# Gimble_Breakout.net
KiCad netlist of a schematic drawn in EAGLE
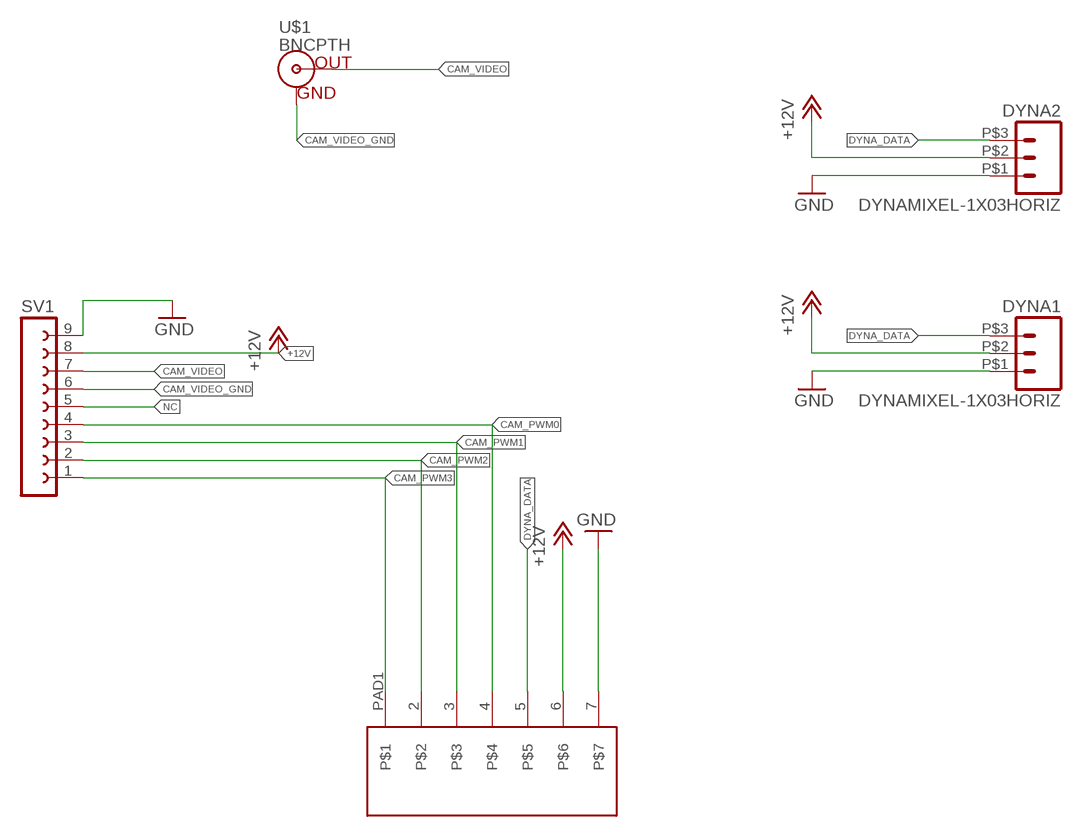
[diagram p0: schematic, sheet 1]

(export (version "E")
  (design (tool "Eeschema 10.0.6"))
  (components
    (comp (ref "DYNA1")
      (value "DYNAMIXEL-1X03HORIZ")
      (footprint "eagle-import:MLX-SPOX5268-3PIN")
      (fields (field (name "MFR") "Molex"))
      (libsource (lib "eagle-import") (part "DYNAMIXEL-1X03HORIZ"))
    )
    (comp (ref "DYNA2")
      (value "DYNAMIXEL-1X03HORIZ")
      (footprint "eagle-import:MLX-SPOX5268-3PIN")
      (fields (field (name "MFR") "Molex"))
      (libsource (lib "eagle-import") (part "DYNAMIXEL-1X03HORIZ"))
    )
    (comp (ref "SV1")
      (value "FE09W")
      (footprint "eagle-import:FE09W")
      (libsource (lib "eagle-import") (part "FE09W"))
    )
    (comp (ref "U$1")
      (value "BNCPTH")
      (footprint "eagle-import:BNC")
      (libsource (lib "eagle-import") (part "BNCPTH"))
    )
    (comp (ref "U$2")
      (value "MOLEX7-PIN")
      (footprint "eagle-import:MOLEX7PIN")
      (libsource (lib "eagle-import") (part "MOLEX7-PIN"))
    )
  )
  (nets
    (net (code "1") (name "+12V") (class "Default")
      (node (ref "DYNA1") (pin "P$2") (pinfunction "2_P$2") (pintype "passive"))
      (node (ref "DYNA2") (pin "P$2") (pinfunction "2_P$2") (pintype "passive"))
      (node (ref "SV1") (pin "8") (pinfunction "8_8") (pintype "passive"))
      (node (ref "U$2") (pin "6") (pinfunction "P$6_6") (pintype "bidirectional"))
    )
    (net (code "2") (name "CAM_PWM0") (class "Default")
      (node (ref "SV1") (pin "4") (pinfunction "4_4") (pintype "passive"))
      (node (ref "U$2") (pin "4") (pinfunction "P$4_4") (pintype "bidirectional"))
    )
    (net (code "3") (name "CAM_PWM1") (class "Default")
      (node (ref "SV1") (pin "3") (pinfunction "3_3") (pintype "passive"))
      (node (ref "U$2") (pin "3") (pinfunction "P$3_3") (pintype "bidirectional"))
    )
    (net (code "4") (name "CAM_PWM2") (class "Default")
      (node (ref "SV1") (pin "2") (pinfunction "2_2") (pintype "passive"))
      (node (ref "U$2") (pin "2") (pinfunction "P$2_2") (pintype "bidirectional"))
    )
    (net (code "5") (name "CAM_PWM3") (class "Default")
      (node (ref "SV1") (pin "1") (pinfunction "1_1") (pintype "passive"))
      (node (ref "U$2") (pin "PAD1") (pinfunction "P$1_PAD1") (pintype "bidirectional"))
    )
    (net (code "6") (name "CAM_VIDEO") (class "Default")
      (node (ref "SV1") (pin "7") (pinfunction "7_7") (pintype "passive"))
      (node (ref "U$1") (pin "S") (pinfunction "OUT_S") (pintype "bidirectional"))
    )
    (net (code "7") (name "CAM_VIDEO_GND") (class "Default")
      (node (ref "SV1") (pin "6") (pinfunction "6_6") (pintype "passive"))
      (node (ref "U$1") (pin "GND") (pinfunction "GND_GND") (pintype "bidirectional"))
    )
    (net (code "8") (name "DYNA_DATA") (class "Default")
      (node (ref "DYNA1") (pin "P$3") (pinfunction "3_P$3") (pintype "passive"))
      (node (ref "DYNA2") (pin "P$3") (pinfunction "3_P$3") (pintype "passive"))
      (node (ref "U$2") (pin "5") (pinfunction "P$5_5") (pintype "bidirectional"))
    )
    (net (code "9") (name "GND") (class "Default")
      (node (ref "DYNA1") (pin "P$1") (pinfunction "1_P$1") (pintype "passive"))
      (node (ref "DYNA2") (pin "P$1") (pinfunction "1_P$1") (pintype "passive"))
      (node (ref "SV1") (pin "9") (pinfunction "9_9") (pintype "passive"))
      (node (ref "U$2") (pin "7") (pinfunction "P$7_7") (pintype "bidirectional"))
    )
    (net (code "10") (name "NC") (class "Default")
      (node (ref "SV1") (pin "5") (pinfunction "5_5") (pintype "passive"))
    )
  )
)
